# Feather_RCSwitch.net
KiCad netlist of a schematic drawn in EAGLE
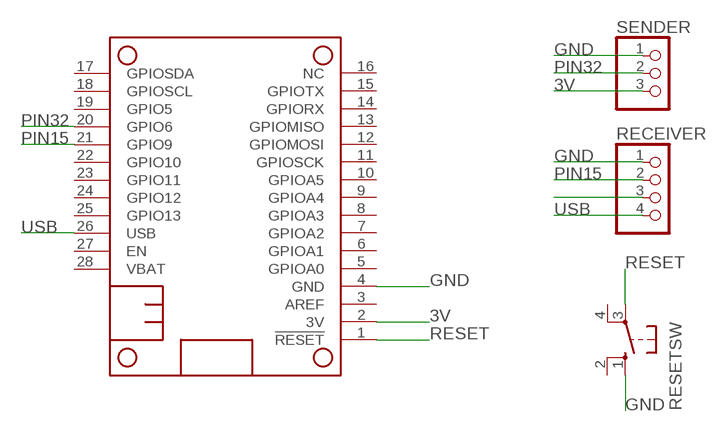
[diagram p0: schematic, sheet 1]

(export (version "E")
  (design (tool "Eeschema 10.0.6"))
  (components
    (comp (ref "MS1")
      (value "FEATHERWING")
      (footprint "eagle-import:FEATHERWING")
      (libsource (lib "eagle-import") (part "FEATHERWING"))
    )
    (comp (ref "RECEIVER")
      (value "PINHD-1X4")
      (footprint "eagle-import:1X04")
      (libsource (lib "eagle-import") (part "PINHD-1X4"))
    )
    (comp (ref "RESETSW")
      (value "10-XX")
      (footprint "eagle-import:B3F-10XX")
      (fields (field (name "MPN") "B3F-1000"))
      (libsource (lib "eagle-import") (part "10-XX"))
    )
    (comp (ref "SENDER")
      (value "PINHD-1X3")
      (footprint "eagle-import:1X03")
      (libsource (lib "eagle-import") (part "PINHD-1X3"))
    )
  )
  (nets
    (net (code "1") (name "/3V") (class "Default")
      (node (ref "MS1") (pin "2") (pinfunction "3V_2") (pintype "power_in"))
      (node (ref "SENDER") (pin "3") (pinfunction "3_3") (pintype "passive"))
    )
    (net (code "2") (name "/GND") (class "Default")
      (node (ref "MS1") (pin "4") (pinfunction "GND_4") (pintype "power_in"))
      (node (ref "RECEIVER") (pin "1") (pinfunction "1_1") (pintype "passive"))
      (node (ref "RESETSW") (pin "1") (pinfunction "S_1") (pintype "passive"))
      (node (ref "SENDER") (pin "1") (pinfunction "1_1") (pintype "passive"))
    )
    (net (code "3") (name "/PIN15") (class "Default")
      (node (ref "MS1") (pin "21") (pinfunction "GPIO9_21") (pintype "bidirectional"))
      (node (ref "RECEIVER") (pin "2") (pinfunction "2_2") (pintype "passive"))
    )
    (net (code "4") (name "/PIN32") (class "Default")
      (node (ref "MS1") (pin "20") (pinfunction "GPIO6_20") (pintype "bidirectional"))
      (node (ref "SENDER") (pin "2") (pinfunction "2_2") (pintype "passive"))
    )
    (net (code "5") (name "/RESET") (class "Default")
      (node (ref "MS1") (pin "1") (pinfunction "~{RESET}_1") (pintype "input"))
      (node (ref "RESETSW") (pin "3") (pinfunction "P_3") (pintype "passive"))
    )
    (net (code "6") (name "/USB") (class "Default")
      (node (ref "MS1") (pin "26") (pinfunction "USB_26") (pintype "power_in"))
      (node (ref "RECEIVER") (pin "4") (pinfunction "4_4") (pintype "passive"))
    )
    (net (code "7") (name "/VBAT") (class "Default")
      (node (ref "MS1") (pin "28") (pinfunction "VBAT_28") (pintype "power_in"))
    )
    (net (code "8") (name "unconnected-(MS1-AREF-Pad3)") (class "Default")
      (node (ref "MS1") (pin "3") (pinfunction "AREF_3") (pintype "passive"))
    )
    (net (code "9") (name "unconnected-(MS1-EN-Pad27)") (class "Default")
      (node (ref "MS1") (pin "27") (pinfunction "EN_27") (pintype "passive"))
    )
    (net (code "10") (name "unconnected-(MS1-GPIO5-Pad19)") (class "Default")
      (node (ref "MS1") (pin "19") (pinfunction "GPIO5_19") (pintype "bidirectional"))
    )
    (net (code "11") (name "unconnected-(MS1-GPIO10-Pad22)") (class "Default")
      (node (ref "MS1") (pin "22") (pinfunction "GPIO10_22") (pintype "bidirectional"))
    )
    (net (code "12") (name "unconnected-(MS1-GPIO11-Pad23)") (class "Default")
      (node (ref "MS1") (pin "23") (pinfunction "GPIO11_23") (pintype "bidirectional"))
    )
    (net (code "13") (name "unconnected-(MS1-GPIO12-Pad24)") (class "Default")
      (node (ref "MS1") (pin "24") (pinfunction "GPIO12_24") (pintype "bidirectional"))
    )
    (net (code "14") (name "unconnected-(MS1-GPIO13-Pad25)") (class "Default")
      (node (ref "MS1") (pin "25") (pinfunction "GPIO13_25") (pintype "bidirectional"))
    )
    (net (code "15") (name "unconnected-(MS1-GPIOA0-Pad5)") (class "Default")
      (node (ref "MS1") (pin "5") (pinfunction "GPIOA0_5") (pintype "bidirectional"))
    )
    (net (code "16") (name "unconnected-(MS1-GPIOA1-Pad6)") (class "Default")
      (node (ref "MS1") (pin "6") (pinfunction "GPIOA1_6") (pintype "bidirectional"))
    )
    (net (code "17") (name "unconnected-(MS1-GPIOA2-Pad7)") (class "Default")
      (node (ref "MS1") (pin "7") (pinfunction "GPIOA2_7") (pintype "bidirectional"))
    )
    (net (code "18") (name "unconnected-(MS1-GPIOA3-Pad8)") (class "Default")
      (node (ref "MS1") (pin "8") (pinfunction "GPIOA3_8") (pintype "bidirectional"))
    )
    (net (code "19") (name "unconnected-(MS1-GPIOA4-Pad9)") (class "Default")
      (node (ref "MS1") (pin "9") (pinfunction "GPIOA4_9") (pintype "bidirectional"))
    )
    (net (code "20") (name "unconnected-(MS1-GPIOA5-Pad10)") (class "Default")
      (node (ref "MS1") (pin "10") (pinfunction "GPIOA5_10") (pintype "bidirectional"))
    )
    (net (code "21") (name "unconnected-(MS1-GPIOMISO-Pad13)") (class "Default")
      (node (ref "MS1") (pin "13") (pinfunction "GPIOMISO_13") (pintype "bidirectional"))
    )
    (net (code "22") (name "unconnected-(MS1-GPIOMOSI-Pad12)") (class "Default")
      (node (ref "MS1") (pin "12") (pinfunction "GPIOMOSI_12") (pintype "bidirectional"))
    )
    (net (code "23") (name "unconnected-(MS1-GPIORX-Pad14)") (class "Default")
      (node (ref "MS1") (pin "14") (pinfunction "GPIORX_14") (pintype "bidirectional"))
    )
    (net (code "24") (name "unconnected-(MS1-GPIOSCK-Pad11)") (class "Default")
      (node (ref "MS1") (pin "11") (pinfunction "GPIOSCK_11") (pintype "bidirectional"))
    )
    (net (code "25") (name "unconnected-(MS1-GPIOSCL-Pad18)") (class "Default")
      (node (ref "MS1") (pin "18") (pinfunction "GPIOSCL_18") (pintype "bidirectional"))
    )
    (net (code "26") (name "unconnected-(MS1-GPIOSDA-Pad17)") (class "Default")
      (node (ref "MS1") (pin "17") (pinfunction "GPIOSDA_17") (pintype "bidirectional"))
    )
    (net (code "27") (name "unconnected-(MS1-GPIOTX-Pad15)") (class "Default")
      (node (ref "MS1") (pin "15") (pinfunction "GPIOTX_15") (pintype "bidirectional"))
    )
    (net (code "28") (name "unconnected-(MS1-NC-Pad16)") (class "Default")
      (node (ref "MS1") (pin "16") (pinfunction "NC_16") (pintype "passive"))
    )
    (net (code "29") (name "unconnected-(RECEIVER-Pad3)") (class "Default")
      (node (ref "RECEIVER") (pin "3") (pinfunction "3_3") (pintype "passive"))
    )
    (net (code "30") (name "unconnected-(RESETSW-P1-Pad4)") (class "Default")
      (node (ref "RESETSW") (pin "4") (pinfunction "P1_4") (pintype "passive"))
    )
    (net (code "31") (name "unconnected-(RESETSW-S1-Pad2)") (class "Default")
      (node (ref "RESETSW") (pin "2") (pinfunction "S1_2") (pintype "passive"))
    )
  )
)
